# MCU.net
KiCad netlist of a schematic drawn in Altium Designer
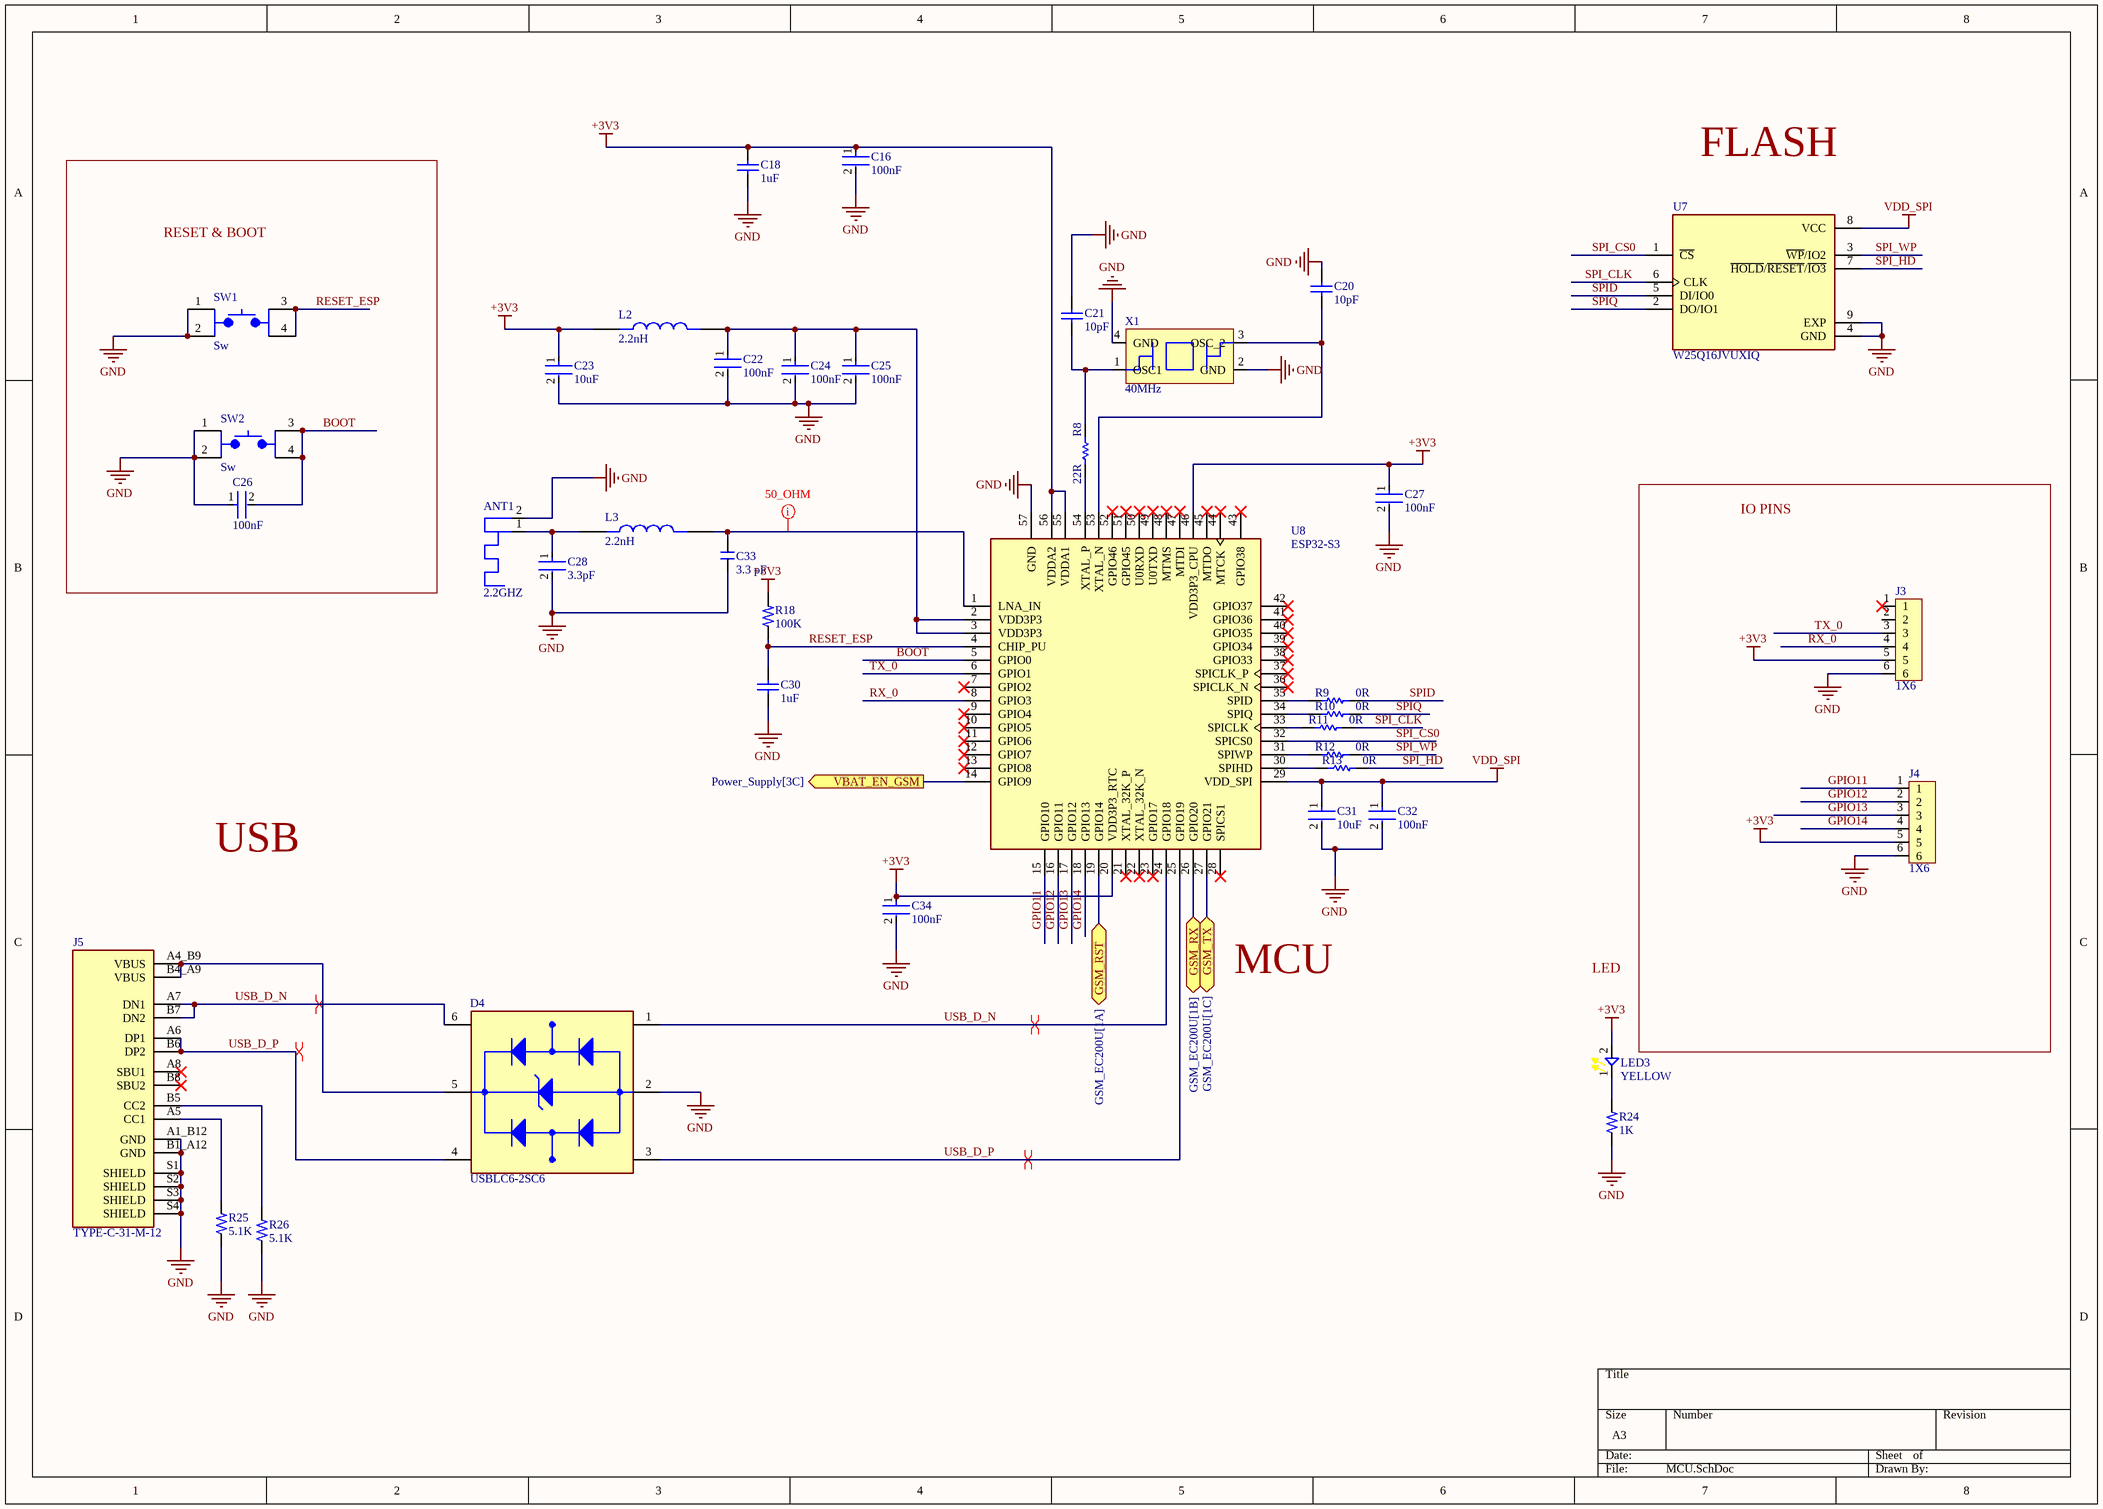
[diagram p0: MCU.SchDoc]

(export (version "E")
  (design (tool "Eeschema 10.0.6"))
  (components
    (comp (ref "ANT1")
      (value "2.2GHZ")
      (footprint "2.4 GHz PCB antenna")
      (libsource (lib "Schlib1") (part "2.4 GHz PCB antenna"))
    )
    (comp (ref "C16")
      (value "100nF")
      (footprint "FP-CGA3E-0_3-0_1-IPC_A")
      (description "Cap Ceramic 100nF 50V X7R 10% Pad SMD 0603 +125°C Automotive T/R")
      (fields (field (name "TOLERANCE") "10%") (field (name "VOLTAGE") "50V"))
      (libsource (lib "Altium Content Vault") (part "b4654b650e69147ec39a6b967a45e02"))
    )
    (comp (ref "C18")
      (value "1uF")
      (footprint "CAPC1608X90X35LL15T15")
      (fields (field (name "MANUFACTURER") "Kemet") (field (name "PART NUMBER") "C0603C105K4RACTU"))
      (libsource (lib "Altium Content Vault") (part "CAP"))
    )
    (comp (ref "C20")
      (value "10pF")
      (footprint "CAPC1608X90X35LL10T15")
      (fields (field (name "PART NUMBER") "GRM1885C1H100JA01D") (field (name "MANUFACTURER") "Murata"))
      (libsource (lib "Altium Content Vault") (part "CAP"))
    )
    (comp (ref "C21")
      (value "10pF")
      (footprint "CAPC1608X90X35LL10T15")
      (fields (field (name "PART NUMBER") "GRM1885C1H100JA01D") (field (name "MANUFACTURER") "Murata"))
      (libsource (lib "Altium Content Vault") (part "CAP"))
    )
    (comp (ref "C22")
      (value "100nF")
      (footprint "FP-CGA3E-0_3-0_1-IPC_A")
      (description "Cap Ceramic 100nF 50V X7R 10% Pad SMD 0603 +125°C Automotive T/R")
      (fields (field (name "TOLERANCE") "10%") (field (name "VOLTAGE") "50V"))
      (libsource (lib "Altium Content Vault") (part "b4654b650e69147ec39a6b967a45e02"))
    )
    (comp (ref "C23")
      (value "10uF")
      (footprint "FP-GRM188-0_1-e0_2_0_55-IPC_A")
      (description "Chip Multilayer Ceramic Capacitors for General Purpose, 0603, 10uF, X5R, 15%, 20%, 6.3V")
      (fields (field (name "VOLTAGE") "6.3V") (field (name "TOLERANCE") "20%"))
      (libsource (lib "Altium Content Vault") (part "02cd4be3c70576c341d710602a673aa"))
    )
    (comp (ref "C24")
      (value "100nF")
      (footprint "FP-CGA3E-0_3-0_1-IPC_A")
      (description "Cap Ceramic 100nF 50V X7R 10% Pad SMD 0603 +125°C Automotive T/R")
      (fields (field (name "TOLERANCE") "10%") (field (name "VOLTAGE") "50V"))
      (libsource (lib "Altium Content Vault") (part "b4654b650e69147ec39a6b967a45e02"))
    )
    (comp (ref "C25")
      (value "100nF")
      (footprint "FP-CGA3E-0_3-0_1-IPC_A")
      (description "Cap Ceramic 100nF 50V X7R 10% Pad SMD 0603 +125°C Automotive T/R")
      (fields (field (name "TOLERANCE") "10%") (field (name "VOLTAGE") "50V"))
      (libsource (lib "Altium Content Vault") (part "b4654b650e69147ec39a6b967a45e02"))
    )
    (comp (ref "C26")
      (value "100nF")
      (footprint "FP-CGA3E-0_3-0_1-IPC_A")
      (description "Cap Ceramic 100nF 50V X7R 10% Pad SMD 0603 +125°C Automotive T/R")
      (fields (field (name "TOLERANCE") "10%") (field (name "VOLTAGE") "50V"))
      (libsource (lib "Altium Content Vault") (part "b4654b650e69147ec39a6b967a45e02"))
    )
    (comp (ref "C27")
      (value "100nF")
      (footprint "FP-CGA3E-0_3-0_1-IPC_A")
      (description "Cap Ceramic 100nF 50V X7R 10% Pad SMD 0603 +125°C Automotive T/R")
      (fields (field (name "TOLERANCE") "10%") (field (name "VOLTAGE") "50V"))
      (libsource (lib "Altium Content Vault") (part "b4654b650e69147ec39a6b967a45e02"))
    )
    (comp (ref "C28")
      (value "3.3pF")
      (footprint "FP-C0603C-CF-MFG")
      (description "CAP CER 3.3PF 50V NP0 0603")
      (fields
        (field (name "TOLERANCE") "0.25 pF")
        (field (name "OCTOPART") "https://octopart.com/c0603c339c5gactu-kemet-3701205")
      )
      (libsource (lib "Altium Content Vault") (part "b4654b650e69147ec39a6b967a45e02"))
    )
    (comp (ref "C30")
      (value "1uF")
      (footprint "CAPC1608X90X35LL15T15")
      (fields (field (name "MANUFACTURER") "Kemet") (field (name "PART NUMBER") "C0603C105K4RACTU"))
      (libsource (lib "Altium Content Vault") (part "CAP"))
    )
    (comp (ref "C31")
      (value "10uF")
      (footprint "FP-GRM188-0_1-e0_2_0_55-IPC_A")
      (description "Chip Multilayer Ceramic Capacitors for General Purpose, 0603, 10uF, X5R, 15%, 20%, 6.3V")
      (fields (field (name "VOLTAGE") "6.3V") (field (name "TOLERANCE") "20%"))
      (libsource (lib "Altium Content Vault") (part "02cd4be3c70576c341d710602a673aa"))
    )
    (comp (ref "C32")
      (value "100nF")
      (footprint "FP-CGA3E-0_3-0_1-IPC_A")
      (description "Cap Ceramic 100nF 50V X7R 10% Pad SMD 0603 +125°C Automotive T/R")
      (fields (field (name "TOLERANCE") "10%") (field (name "VOLTAGE") "50V"))
      (libsource (lib "Altium Content Vault") (part "b4654b650e69147ec39a6b967a45e02"))
    )
    (comp (ref "C33")
      (value "3.3 pF")
      (footprint "Capacitor_0805")
      (description "Multilayer Ceramic Capacitor, 3.3 pF, 50 V, ± 0.1pF, C0G (NP0), 0805 [2012 Metric]")
      (fields
        (field (name "MANUFACTURER") "Yageo")
        (field (name "MANUFACTURER PART NUMBER") "CC0805BRNPO9BN3R3")
      )
      (libsource (lib "Schlib1") (part "CAP 3.3 pF 0805"))
    )
    (comp (ref "C34")
      (value "100nF")
      (footprint "FP-CGA3E-0_3-0_1-IPC_A")
      (description "Cap Ceramic 100nF 50V X7R 10% Pad SMD 0603 +125°C Automotive T/R")
      (fields (field (name "TOLERANCE") "10%") (field (name "VOLTAGE") "50V"))
      (libsource (lib "Altium Content Vault") (part "b4654b650e69147ec39a6b967a45e02"))
    )
    (comp (ref "D4")
      (value "USBLC6-2SC6")
      (footprint "SOT-23-6")
      (description "ESD Suppressor Diode Array Dual Uni-Dir 15kV Air Gap/15kV Contact Disc 6-Pin SOT-23 T/R")
      (fields (field (name "MANUFACTURER") "STMicroelectronics"))
      (libsource (lib "Schlib1") (part "USBLC6-2SC6"))
    )
    (comp (ref "J3")
      (value "1X6")
      (footprint "Header_1X6_2.54mm")
      (description "THT Vertical Pin Header WR-PHD, Pitch 2.54 mm, Single Row, 6 pins")
      (fields
        (field (name "MANUFACTURER") "Wurth Electronics")
        (field (name "MANUFACTURER PART NUMBER") "61300611121")
      )
      (libsource (lib "Schlib1") (part "Header Male 1X6"))
    )
    (comp (ref "J4")
      (value "1X6")
      (footprint "Header_1X6_2.54mm")
      (description "THT Vertical Pin Header WR-PHD, Pitch 2.54 mm, Single Row, 6 pins")
      (fields
        (field (name "MANUFACTURER") "Wurth Electronics")
        (field (name "MANUFACTURER PART NUMBER") "61300611121")
      )
      (libsource (lib "Schlib1") (part "Header Male 1X6"))
    )
    (comp (ref "J5")
      (value "TYPE-C-31-M-12")
      (footprint "TYPE-C-31-M-12")
      (fields (field (name "MANUFACTURER") "HRO Electronics"))
      (libsource (lib "Schlib1") (part "TYPE-C-31-M-12"))
    )
    (comp (ref "L2")
      (value "2.2nH")
      (footprint "Inductor_0603")
      (description "2nH 0603 Inductors (SMD) ROHS")
      (fields
        (field (name "MANUFACTURER") "FH (Guangdong Fenghua Advanced Tech)")
        (field (name "MANUFACTURER PART NUMBER") "VHF160808H2N0ST")
      )
      (libsource (lib "Schlib1") (part "Inductor 2.2nH 0603"))
    )
    (comp (ref "L3")
      (value "2.2nH")
      (footprint "Inductor_0603")
      (description "2nH 0603 Inductors (SMD) ROHS")
      (fields
        (field (name "MANUFACTURER") "FH (Guangdong Fenghua Advanced Tech)")
        (field (name "MANUFACTURER PART NUMBER") "VHF160808H2N0ST")
      )
      (libsource (lib "Schlib1") (part "Inductor 2.2nH 0603"))
    )
    (comp (ref "LED3")
      (value "YELLOW")
      (footprint "LED_YELLOW_0603")
      (description "TJ-S1608SW6TGLCCW-A5")
      (fields (field (name "MANUFACTURER") "Togialed"))
      (libsource (lib "Schlib1") (part "LED_Yellow_0603"))
    )
    (comp (ref "R8")
      (value "22R")
      (footprint "RESC1608X55X25NL10T15")
      (description "Chip Resistor, 22 Ohm, +/- 1%, 0.1 W, -55 to 155 degC, 0603 (1608 Metric), RoHS, Tape and Reel")
      (libsource (lib "Altium Content Vault") (part "RES-2"))
    )
    (comp (ref "R9")
      (value "0R")
      (footprint "RESC1609X50X30NL8T20")
      (description "Chip Resistor, 0 Ohm, Jumper, 100 mW, -55 to 155 degC, 0603 (1608 Metric), RoHS, Tape and Reel")
      (fields (field (name "MANUFACTURER") "Vishay Semiconductor"))
      (libsource (lib "Altium Content Vault") (part "RES-2"))
    )
    (comp (ref "R10")
      (value "0R")
      (footprint "RESC1609X50X30NL8T20")
      (description "Chip Resistor, 0 Ohm, Jumper, 100 mW, -55 to 155 degC, 0603 (1608 Metric), RoHS, Tape and Reel")
      (fields (field (name "MANUFACTURER") "Vishay Semiconductor"))
      (libsource (lib "Altium Content Vault") (part "RES-2"))
    )
    (comp (ref "R11")
      (value "0R")
      (footprint "RESC1609X50X30NL8T20")
      (description "Chip Resistor, 0 Ohm, Jumper, 100 mW, -55 to 155 degC, 0603 (1608 Metric), RoHS, Tape and Reel")
      (fields (field (name "MANUFACTURER") "Vishay Semiconductor"))
      (libsource (lib "Altium Content Vault") (part "RES-2"))
    )
    (comp (ref "R12")
      (value "0R")
      (footprint "RESC1609X50X30NL8T20")
      (description "Chip Resistor, 0 Ohm, Jumper, 100 mW, -55 to 155 degC, 0603 (1608 Metric), RoHS, Tape and Reel")
      (fields (field (name "MANUFACTURER") "Vishay Semiconductor"))
      (libsource (lib "Altium Content Vault") (part "RES-2"))
    )
    (comp (ref "R13")
      (value "0R")
      (footprint "RESC1609X50X30NL8T20")
      (description "Chip Resistor, 0 Ohm, Jumper, 100 mW, -55 to 155 degC, 0603 (1608 Metric), RoHS, Tape and Reel")
      (fields (field (name "MANUFACTURER") "Vishay Semiconductor"))
      (libsource (lib "Altium Content Vault") (part "RES-2"))
    )
    (comp (ref "R18")
      (value "100K")
      (footprint "Resistor_0603")
      (description "Res Thick Film 0603 100K Ohm 1% 0.1W(1/10W) ±100ppm/C Pad SMD Automotive T/R")
      (fields
        (field (name "MANUFACTURER") "Stackpole Electronics")
        (field (name "MANUFACTURER PART NUMBER") "RMCF0603FT100K")
      )
      (libsource (lib "Schlib1") (part "R_100K_0603"))
    )
    (comp (ref "R24")
      (value "1K")
      (footprint "Resistor_0805")
      (description "125Mw Thick Film Resistors 100Ppm/ 1% 1K 0805 Chip Resistor Surface Mount Rohs")
      (fields
        (field (name "MANUFACTURER") "Yageo")
        (field (name "MANUFACTURER PART NUMBER") "RC0805FR-071KL")
      )
      (libsource (lib "Schlib1") (part "Res 1K 0805"))
    )
    (comp (ref "R25")
      (value "5.1K")
      (footprint "Resistor_0805")
      (description "Res Thin Film 0805 5.1K Ohm 0.1% 1/8W ±10ppm/°C Molded SMD Paper T/R")
      (fields
        (field (name "MANUFACTURER") "Yageo")
        (field (name "MANUFACTURER PART NUMBER") "RT0805BRD075K1L")
      )
      (libsource (lib "Schlib1") (part "RES 5.1K 0805"))
    )
    (comp (ref "R26")
      (value "5.1K")
      (footprint "Resistor_0805")
      (description "Res Thin Film 0805 5.1K Ohm 0.1% 1/8W ±10ppm/°C Molded SMD Paper T/R")
      (fields
        (field (name "MANUFACTURER") "Yageo")
        (field (name "MANUFACTURER PART NUMBER") "RT0805BRD075K1L")
      )
      (libsource (lib "Schlib1") (part "RES 5.1K 0805"))
    )
    (comp (ref "SW1")
      (value "Sw")
      (footprint "SW_Tactile_SMD")
      (description "TL3305A Series SPST 12 V 4.5 x 4.5 mm 260 gf Top Actuated SMT Tactile Switch")
      (fields
        (field (name "MANUFACTURER") "E-Switch")
        (field (name "MANUFACTURER PART NUMBER") "TL3305AF260QG")
      )
      (libsource (lib "Schlib1") (part "SW_Tactile_SPST"))
    )
    (comp (ref "SW2")
      (value "Sw")
      (footprint "SW_Tactile_SMD")
      (description "TL3305A Series SPST 12 V 4.5 x 4.5 mm 260 gf Top Actuated SMT Tactile Switch")
      (fields
        (field (name "MANUFACTURER") "E-Switch")
        (field (name "MANUFACTURER PART NUMBER") "TL3305AF260QG")
      )
      (libsource (lib "Schlib1") (part "SW_Tactile_SPST"))
    )
    (comp (ref "U7")
      (value "W25Q16JVUXIQ")
      (footprint "8_USON")
      (description "NOR Flash Serial (SPI, Dual SPI, Quad SPI) 3V/3.3V 16M-bit 2M x 8 6ns 8-Pin USON EP T/R")
      (fields
        (field (name "MANUFACTURER") "Winbond")
        (field (name "MANUFACTURER PART NUMBER") "W25Q16JVUXIQ TR")
      )
      (libsource (lib "Schlib1") (part "W25Q16JVUXIQ TR"))
    )
    (comp (ref "U8")
      (value "ESP32-S3")
      (footprint "ESP32S3")
      (description "RF System on a Chip - SoC SMD IC, Dual-Core MCU, Wi-Fi 2.4G BLE 5.0 Combo")
      (fields
        (field (name "MANUFACTURER") "Espressif Systems")
        (field (name "MANUFACTURER PART NUMBER") "ESP32-S3R8")
      )
      (libsource (lib "Schlib1") (part "ESP32-S3R8"))
    )
    (comp (ref "X1")
      (value "40MHz")
      (footprint "SMD2520-4P")
      (fields
        (field (name "MANUFACTURER") "Seiko")
        (field (name "MANUFACTURER PART NUMBER") "Q24FA20H0020900")
      )
      (libsource (lib "Schlib1") (part "Q24FA20H0020900"))
    )
  )
  (nets
    (net (code "1") (name "+3V3") (class "Default")
      (node (ref "C16") (pin "1") (pinfunction "1_1") (pintype "passive"))
      (node (ref "C18") (pin "2") (pinfunction "2_2") (pintype "passive"))
      (node (ref "C23") (pin "1") (pinfunction "1_1") (pintype "passive"))
      (node (ref "C27") (pin "1") (pinfunction "1_1") (pintype "passive"))
      (node (ref "C34") (pin "1") (pinfunction "1_1") (pintype "passive"))
      (node (ref "J3") (pin "5") (pinfunction "5_5") (pintype "passive"))
      (node (ref "J4") (pin "5") (pinfunction "5_5") (pintype "passive"))
      (node (ref "L2") (pin "1") (pinfunction "1_1") (pintype "passive"))
      (node (ref "LED3") (pin "2") (pinfunction "2_2") (pintype "passive"))
      (node (ref "R18") (pin "2") (pinfunction "2_2") (pintype "passive"))
      (node (ref "U8") (pin "20") (pinfunction "VDD3P3_RTC_20") (pintype "passive"))
      (node (ref "U8") (pin "46") (pinfunction "VDD3P3_CPU_46") (pintype "passive"))
      (node (ref "U8") (pin "55") (pinfunction "VDDA1_55") (pintype "passive"))
      (node (ref "U8") (pin "56") (pinfunction "VDDA2_56") (pintype "passive"))
    )
    (net (code "2") (name "/BOOT") (class "Default")
      (node (ref "C26") (pin "2") (pinfunction "2_2") (pintype "passive"))
      (node (ref "SW2") (pin "3") (pinfunction "3_3") (pintype "passive"))
      (node (ref "SW2") (pin "4") (pinfunction "4_4") (pintype "passive"))
      (node (ref "U8") (pin "5") (pinfunction "GPIO0_5") (pintype "passive"))
    )
    (net (code "3") (name "/GPIO11") (class "Default")
      (node (ref "J4") (pin "1") (pinfunction "1_1") (pintype "passive"))
      (node (ref "U8") (pin "15") (pinfunction "GPIO10_15") (pintype "passive"))
    )
    (net (code "4") (name "/GPIO12") (class "Default")
      (node (ref "J4") (pin "2") (pinfunction "2_2") (pintype "passive"))
      (node (ref "U8") (pin "16") (pinfunction "GPIO11_16") (pintype "passive"))
    )
    (net (code "5") (name "/GPIO13") (class "Default")
      (node (ref "J4") (pin "3") (pinfunction "3_3") (pintype "passive"))
      (node (ref "U8") (pin "17") (pinfunction "GPIO12_17") (pintype "passive"))
    )
    (net (code "6") (name "/GPIO14") (class "Default")
      (node (ref "J4") (pin "4") (pinfunction "4_4") (pintype "passive"))
      (node (ref "U8") (pin "18") (pinfunction "GPIO13_18") (pintype "passive"))
    )
    (net (code "7") (name "/GSM_RST") (class "Default")
      (node (ref "U8") (pin "19") (pinfunction "GPIO14_19") (pintype "passive"))
    )
    (net (code "8") (name "/GSM_RX") (class "Default")
      (node (ref "U8") (pin "26") (pinfunction "GPIO20_26") (pintype "passive"))
    )
    (net (code "9") (name "/GSM_TX") (class "Default")
      (node (ref "U8") (pin "27") (pinfunction "GPIO21_27") (pintype "passive"))
    )
    (net (code "10") (name "/RESET_ESP") (class "Default")
      (node (ref "C30") (pin "2") (pinfunction "2_2") (pintype "passive"))
      (node (ref "R18") (pin "1") (pinfunction "1_1") (pintype "passive"))
      (node (ref "SW1") (pin "3") (pinfunction "3_3") (pintype "passive"))
      (node (ref "SW1") (pin "4") (pinfunction "4_4") (pintype "passive"))
      (node (ref "U8") (pin "4") (pinfunction "CHIP_PU_4") (pintype "passive"))
    )
    (net (code "11") (name "/RX_0") (class "Default")
      (node (ref "J3") (pin "4") (pinfunction "4_4") (pintype "passive"))
      (node (ref "U8") (pin "8") (pinfunction "GPIO3_8") (pintype "passive"))
    )
    (net (code "12") (name "/SPID") (class "Default")
      (node (ref "R9") (pin "2") (pinfunction "2_2") (pintype "passive"))
      (node (ref "U7") (pin "5") (pinfunction "DI/IO0_5") (pintype "passive"))
    )
    (net (code "13") (name "/SPIQ") (class "Default")
      (node (ref "R10") (pin "2") (pinfunction "2_2") (pintype "passive"))
      (node (ref "U7") (pin "2") (pinfunction "DO/IO1_2") (pintype "passive"))
    )
    (net (code "14") (name "/SPI_CLK") (class "Default")
      (node (ref "R11") (pin "2") (pinfunction "2_2") (pintype "passive"))
      (node (ref "U7") (pin "6") (pinfunction "CLK_6") (pintype "passive"))
    )
    (net (code "15") (name "/SPI_CS0") (class "Default")
      (node (ref "U7") (pin "1") (pinfunction "~{CS}_1") (pintype "passive"))
      (node (ref "U8") (pin "32") (pinfunction "SPICS0_32") (pintype "passive"))
    )
    (net (code "16") (name "/SPI_HD") (class "Default")
      (node (ref "R13") (pin "2") (pinfunction "2_2") (pintype "passive"))
      (node (ref "U7") (pin "7") (pinfunction "~{HOLD}/~{RESET}/~{IO3}_7") (pintype "passive"))
    )
    (net (code "17") (name "/SPI_WP") (class "Default")
      (node (ref "R12") (pin "2") (pinfunction "2_2") (pintype "passive"))
      (node (ref "U7") (pin "3") (pinfunction "~{WP}/IO2_3") (pintype "passive"))
    )
    (net (code "18") (name "/TX_0") (class "Default")
      (node (ref "J3") (pin "3") (pinfunction "3_3") (pintype "passive"))
      (node (ref "U8") (pin "6") (pinfunction "GPIO1_6") (pintype "passive"))
    )
    (net (code "19") (name "/USB_D_N") (class "Default")
      (node (ref "D4") (pin "1") (pinfunction "I/O1_IN_1") (pintype "passive"))
      (node (ref "D4") (pin "6") (pinfunction "I/O1_OUT_6") (pintype "passive"))
      (node (ref "J5") (pin "A7") (pinfunction "DN1_A7") (pintype "passive"))
      (node (ref "J5") (pin "B7") (pinfunction "DN2_B7") (pintype "passive"))
      (node (ref "U8") (pin "24") (pinfunction "GPIO18_24") (pintype "passive"))
    )
    (net (code "20") (name "/USB_D_P") (class "Default")
      (node (ref "D4") (pin "3") (pinfunction "I/O2_IN_3") (pintype "passive"))
      (node (ref "D4") (pin "4") (pinfunction "I/O2_OUT_4") (pintype "passive"))
      (node (ref "J5") (pin "A6") (pinfunction "DP1_A6") (pintype "passive"))
      (node (ref "J5") (pin "B6") (pinfunction "DP2_B6") (pintype "passive"))
      (node (ref "U8") (pin "25") (pinfunction "GPIO19_25") (pintype "passive"))
    )
    (net (code "21") (name "/VBAT_EN_GSM") (class "Default")
      (node (ref "U8") (pin "14") (pinfunction "GPIO9_14") (pintype "passive"))
    )
    (net (code "22") (name "GND") (class "Default")
      (node (ref "ANT1") (pin "2") (pinfunction "2_2") (pintype "passive"))
      (node (ref "C16") (pin "2") (pinfunction "2_2") (pintype "passive"))
      (node (ref "C18") (pin "1") (pinfunction "1_1") (pintype "passive"))
      (node (ref "C20") (pin "2") (pinfunction "2_2") (pintype "passive"))
      (node (ref "C21") (pin "2") (pinfunction "2_2") (pintype "passive"))
      (node (ref "C22") (pin "2") (pinfunction "2_2") (pintype "passive"))
      (node (ref "C23") (pin "2") (pinfunction "2_2") (pintype "passive"))
      (node (ref "C24") (pin "2") (pinfunction "2_2") (pintype "passive"))
      (node (ref "C25") (pin "2") (pinfunction "2_2") (pintype "passive"))
      (node (ref "C26") (pin "1") (pinfunction "1_1") (pintype "passive"))
      (node (ref "C27") (pin "2") (pinfunction "2_2") (pintype "passive"))
      (node (ref "C28") (pin "2") (pinfunction "2_2") (pintype "passive"))
      (node (ref "C30") (pin "1") (pinfunction "1_1") (pintype "passive"))
      (node (ref "C31") (pin "2") (pinfunction "2_2") (pintype "passive"))
      (node (ref "C32") (pin "2") (pinfunction "2_2") (pintype "passive"))
      (node (ref "C33") (pin "1") (pinfunction "1_1") (pintype "passive"))
      (node (ref "C34") (pin "2") (pinfunction "2_2") (pintype "passive"))
      (node (ref "D4") (pin "2") (pinfunction "GND_2") (pintype "power_in"))
      (node (ref "J3") (pin "6") (pinfunction "6_6") (pintype "passive"))
      (node (ref "J4") (pin "6") (pinfunction "6_6") (pintype "passive"))
      (node (ref "J5") (pin "A1_B12") (pinfunction "GND_A1_B12") (pintype "passive"))
      (node (ref "J5") (pin "B1_A12") (pinfunction "GND_B1_A12") (pintype "passive"))
      (node (ref "J5") (pin "S1") (pinfunction "SHIELD_S1") (pintype "passive"))
      (node (ref "J5") (pin "S2") (pinfunction "SHIELD_S2") (pintype "passive"))
      (node (ref "J5") (pin "S3") (pinfunction "SHIELD_S3") (pintype "passive"))
      (node (ref "J5") (pin "S4") (pinfunction "SHIELD_S4") (pintype "passive"))
      (node (ref "R24") (pin "1") (pinfunction "1_1") (pintype "passive"))
      (node (ref "R25") (pin "1") (pinfunction "1_1") (pintype "passive"))
      (node (ref "R26") (pin "1") (pinfunction "1_1") (pintype "passive"))
      (node (ref "SW1") (pin "1") (pinfunction "1_1") (pintype "passive"))
      (node (ref "SW1") (pin "2") (pinfunction "2_2") (pintype "passive"))
      (node (ref "SW2") (pin "1") (pinfunction "1_1") (pintype "passive"))
      (node (ref "SW2") (pin "2") (pinfunction "2_2") (pintype "passive"))
      (node (ref "U7") (pin "4") (pinfunction "GND_4") (pintype "passive"))
      (node (ref "U7") (pin "9") (pinfunction "EXP_9") (pintype "passive"))
      (node (ref "U8") (pin "57") (pinfunction "GND_57") (pintype "passive"))
      (node (ref "X1") (pin "2") (pinfunction "GND_2") (pintype "passive"))
      (node (ref "X1") (pin "4") (pinfunction "GND_4") (pintype "passive"))
    )
    (net (code "23") (name "Net-(ANT1-Pad1)") (class "Default")
      (node (ref "ANT1") (pin "1") (pinfunction "1_1") (pintype "passive"))
      (node (ref "C28") (pin "1") (pinfunction "1_1") (pintype "passive"))
      (node (ref "L3") (pin "1") (pinfunction "1_1") (pintype "passive"))
    )
    (net (code "24") (name "Net-(C22-Pad1)") (class "Default")
      (node (ref "C22") (pin "1") (pinfunction "1_1") (pintype "passive"))
      (node (ref "C24") (pin "1") (pinfunction "1_1") (pintype "passive"))
      (node (ref "C25") (pin "1") (pinfunction "1_1") (pintype "passive"))
      (node (ref "L2") (pin "2") (pinfunction "2_2") (pintype "passive"))
      (node (ref "U8") (pin "2") (pinfunction "VDD3P3_2") (pintype "passive"))
      (node (ref "U8") (pin "3") (pinfunction "VDD3P3_3") (pintype "passive"))
    )
    (net (code "25") (name "Net-(D4-VBUS)") (class "Default")
      (node (ref "D4") (pin "5") (pinfunction "VBUS_5") (pintype "power_in"))
      (node (ref "J5") (pin "A4_B9") (pinfunction "VBUS_A4_B9") (pintype "passive"))
      (node (ref "J5") (pin "B4_A9") (pinfunction "VBUS_B4_A9") (pintype "passive"))
    )
    (net (code "26") (name "Net-(J5-CC1)") (class "Default")
      (node (ref "J5") (pin "A5") (pinfunction "CC1_A5") (pintype "passive"))
      (node (ref "R25") (pin "2") (pinfunction "2_2") (pintype "passive"))
    )
    (net (code "27") (name "Net-(J5-CC2)") (class "Default")
      (node (ref "J5") (pin "B5") (pinfunction "CC2_B5") (pintype "passive"))
      (node (ref "R26") (pin "2") (pinfunction "2_2") (pintype "passive"))
    )
    (net (code "28") (name "Net-(LED3-Pad1)") (class "Default")
      (node (ref "LED3") (pin "1") (pinfunction "1_1") (pintype "passive"))
      (node (ref "R24") (pin "2") (pinfunction "2_2") (pintype "passive"))
    )
    (net (code "29") (name "Net-(U8-LNA_IN)") (class "Default")
      (node (ref "C33") (pin "2") (pinfunction "2_2") (pintype "passive"))
      (node (ref "L3") (pin "2") (pinfunction "2_2") (pintype "passive"))
      (node (ref "U8") (pin "1") (pinfunction "LNA_IN_1") (pintype "passive"))
    )
    (net (code "30") (name "Net-(U8-SPICLK)") (class "Default")
      (node (ref "R11") (pin "1") (pinfunction "1_1") (pintype "passive"))
      (node (ref "U8") (pin "33") (pinfunction "SPICLK_33") (pintype "passive"))
    )
    (net (code "31") (name "Net-(U8-SPID)") (class "Default")
      (node (ref "R9") (pin "1") (pinfunction "1_1") (pintype "passive"))
      (node (ref "U8") (pin "35") (pinfunction "SPID_35") (pintype "passive"))
    )
    (net (code "32") (name "Net-(U8-SPIHD)") (class "Default")
      (node (ref "R13") (pin "1") (pinfunction "1_1") (pintype "passive"))
      (node (ref "U8") (pin "30") (pinfunction "SPIHD_30") (pintype "passive"))
    )
    (net (code "33") (name "Net-(U8-SPIQ)") (class "Default")
      (node (ref "R10") (pin "1") (pinfunction "1_1") (pintype "passive"))
      (node (ref "U8") (pin "34") (pinfunction "SPIQ_34") (pintype "passive"))
    )
    (net (code "34") (name "Net-(U8-SPIWP)") (class "Default")
      (node (ref "R12") (pin "1") (pinfunction "1_1") (pintype "passive"))
      (node (ref "U8") (pin "31") (pinfunction "SPIWP_31") (pintype "passive"))
    )
    (net (code "35") (name "Net-(U8-XTAL_N)") (class "Default")
      (node (ref "C20") (pin "1") (pinfunction "1_1") (pintype "passive"))
      (node (ref "U8") (pin "53") (pinfunction "XTAL_N_53") (pintype "passive"))
      (node (ref "X1") (pin "3") (pinfunction "OSC_2_3") (pintype "passive"))
    )
    (net (code "36") (name "Net-(U8-XTAL_P)") (class "Default")
      (node (ref "R8") (pin "1") (pinfunction "1_1") (pintype "passive"))
      (node (ref "U8") (pin "54") (pinfunction "XTAL_P_54") (pintype "passive"))
    )
    (net (code "37") (name "Net-(X1-OSC1)") (class "Default")
      (node (ref "C21") (pin "1") (pinfunction "1_1") (pintype "passive"))
      (node (ref "R8") (pin "2") (pinfunction "2_2") (pintype "passive"))
      (node (ref "X1") (pin "1") (pinfunction "OSC1_1") (pintype "passive"))
    )
    (net (code "38") (name "VDD_SPI") (class "Default")
      (node (ref "C31") (pin "1") (pinfunction "1_1") (pintype "passive"))
      (node (ref "C32") (pin "1") (pinfunction "1_1") (pintype "passive"))
      (node (ref "U7") (pin "8") (pinfunction "VCC_8") (pintype "passive"))
      (node (ref "U8") (pin "29") (pinfunction "VDD_SPI_29") (pintype "passive"))
    )
    (net (code "39") (name "unconnected-(J3-Pad1)") (class "Default")
      (node (ref "J3") (pin "1") (pinfunction "1_1") (pintype "passive+no_connect"))
    )
    (net (code "40") (name "unconnected-(J3-Pad2)") (class "Default")
      (node (ref "J3") (pin "2") (pinfunction "2_2") (pintype "passive"))
    )
    (net (code "41") (name "unconnected-(J5-SBU1-PadA8)") (class "Default")
      (node (ref "J5") (pin "A8") (pinfunction "SBU1_A8") (pintype "passive+no_connect"))
    )
    (net (code "42") (name "unconnected-(J5-SBU2-PadB8)") (class "Default")
      (node (ref "J5") (pin "B8") (pinfunction "SBU2_B8") (pintype "passive+no_connect"))
    )
    (net (code "43") (name "unconnected-(U8-GPIO2-Pad7)") (class "Default")
      (node (ref "U8") (pin "7") (pinfunction "GPIO2_7") (pintype "passive+no_connect"))
    )
    (net (code "44") (name "unconnected-(U8-GPIO4-Pad9)") (class "Default")
      (node (ref "U8") (pin "9") (pinfunction "GPIO4_9") (pintype "passive+no_connect"))
    )
    (net (code "45") (name "unconnected-(U8-GPIO5-Pad10)") (class "Default")
      (node (ref "U8") (pin "10") (pinfunction "GPIO5_10") (pintype "passive+no_connect"))
    )
    (net (code "46") (name "unconnected-(U8-GPIO6-Pad11)") (class "Default")
      (node (ref "U8") (pin "11") (pinfunction "GPIO6_11") (pintype "passive+no_connect"))
    )
    (net (code "47") (name "unconnected-(U8-GPIO7-Pad12)") (class "Default")
      (node (ref "U8") (pin "12") (pinfunction "GPIO7_12") (pintype "passive+no_connect"))
    )
    (net (code "48") (name "unconnected-(U8-GPIO8-Pad13)") (class "Default")
      (node (ref "U8") (pin "13") (pinfunction "GPIO8_13") (pintype "passive+no_connect"))
    )
    (net (code "49") (name "unconnected-(U8-GPIO17-Pad23)") (class "Default")
      (node (ref "U8") (pin "23") (pinfunction "GPIO17_23") (pintype "passive+no_connect"))
    )
    (net (code "50") (name "unconnected-(U8-GPIO33-Pad38)") (class "Default")
      (node (ref "U8") (pin "38") (pinfunction "GPIO33_38") (pintype "passive+no_connect"))
    )
    (net (code "51") (name "unconnected-(U8-GPIO34-Pad39)") (class "Default")
      (node (ref "U8") (pin "39") (pinfunction "GPIO34_39") (pintype "passive+no_connect"))
    )
    (net (code "52") (name "unconnected-(U8-GPIO35-Pad40)") (class "Default")
      (node (ref "U8") (pin "40") (pinfunction "GPIO35_40") (pintype "passive+no_connect"))
    )
    (net (code "53") (name "unconnected-(U8-GPIO36-Pad41)") (class "Default")
      (node (ref "U8") (pin "41") (pinfunction "GPIO36_41") (pintype "passive+no_connect"))
    )
    (net (code "54") (name "unconnected-(U8-GPIO37-Pad42)") (class "Default")
      (node (ref "U8") (pin "42") (pinfunction "GPIO37_42") (pintype "passive+no_connect"))
    )
    (net (code "55") (name "unconnected-(U8-GPIO38-Pad43)") (class "Default")
      (node (ref "U8") (pin "43") (pinfunction "GPIO38_43") (pintype "passive+no_connect"))
    )
    (net (code "56") (name "unconnected-(U8-GPIO45-Pad51)") (class "Default")
      (node (ref "U8") (pin "51") (pinfunction "GPIO45_51") (pintype "passive+no_connect"))
    )
    (net (code "57") (name "unconnected-(U8-GPIO46-Pad52)") (class "Default")
      (node (ref "U8") (pin "52") (pinfunction "GPIO46_52") (pintype "passive+no_connect"))
    )
    (net (code "58") (name "unconnected-(U8-MTCK-Pad44)") (class "Default")
      (node (ref "U8") (pin "44") (pinfunction "MTCK_44") (pintype "passive+no_connect"))
    )
    (net (code "59") (name "unconnected-(U8-MTDI-Pad47)") (class "Default")
      (node (ref "U8") (pin "47") (pinfunction "MTDI_47") (pintype "passive+no_connect"))
    )
    (net (code "60") (name "unconnected-(U8-MTDO-Pad45)") (class "Default")
      (node (ref "U8") (pin "45") (pinfunction "MTDO_45") (pintype "passive+no_connect"))
    )
    (net (code "61") (name "unconnected-(U8-MTMS-Pad48)") (class "Default")
      (node (ref "U8") (pin "48") (pinfunction "MTMS_48") (pintype "passive+no_connect"))
    )
    (net (code "62") (name "unconnected-(U8-SPICLK_N-Pad36)") (class "Default")
      (node (ref "U8") (pin "36") (pinfunction "SPICLK_N_36") (pintype "passive+no_connect"))
    )
    (net (code "63") (name "unconnected-(U8-SPICLK_P-Pad37)") (class "Default")
      (node (ref "U8") (pin "37") (pinfunction "SPICLK_P_37") (pintype "passive+no_connect"))
    )
    (net (code "64") (name "unconnected-(U8-SPICS1-Pad28)") (class "Default")
      (node (ref "U8") (pin "28") (pinfunction "SPICS1_28") (pintype "passive+no_connect"))
    )
    (net (code "65") (name "unconnected-(U8-U0RXD-Pad50)") (class "Default")
      (node (ref "U8") (pin "50") (pinfunction "U0RXD_50") (pintype "passive+no_connect"))
    )
    (net (code "66") (name "unconnected-(U8-U0TXD-Pad49)") (class "Default")
      (node (ref "U8") (pin "49") (pinfunction "U0TXD_49") (pintype "passive+no_connect"))
    )
    (net (code "67") (name "unconnected-(U8-XTAL_32K_N-Pad22)") (class "Default")
      (node (ref "U8") (pin "22") (pinfunction "XTAL_32K_N_22") (pintype "passive+no_connect"))
    )
    (net (code "68") (name "unconnected-(U8-XTAL_32K_P-Pad21)") (class "Default")
      (node (ref "U8") (pin "21") (pinfunction "XTAL_32K_P_21") (pintype "passive+no_connect"))
    )
  )
)
